# DC_DC_5V_1.net
KiCad netlist of a schematic drawn in Altium Designer
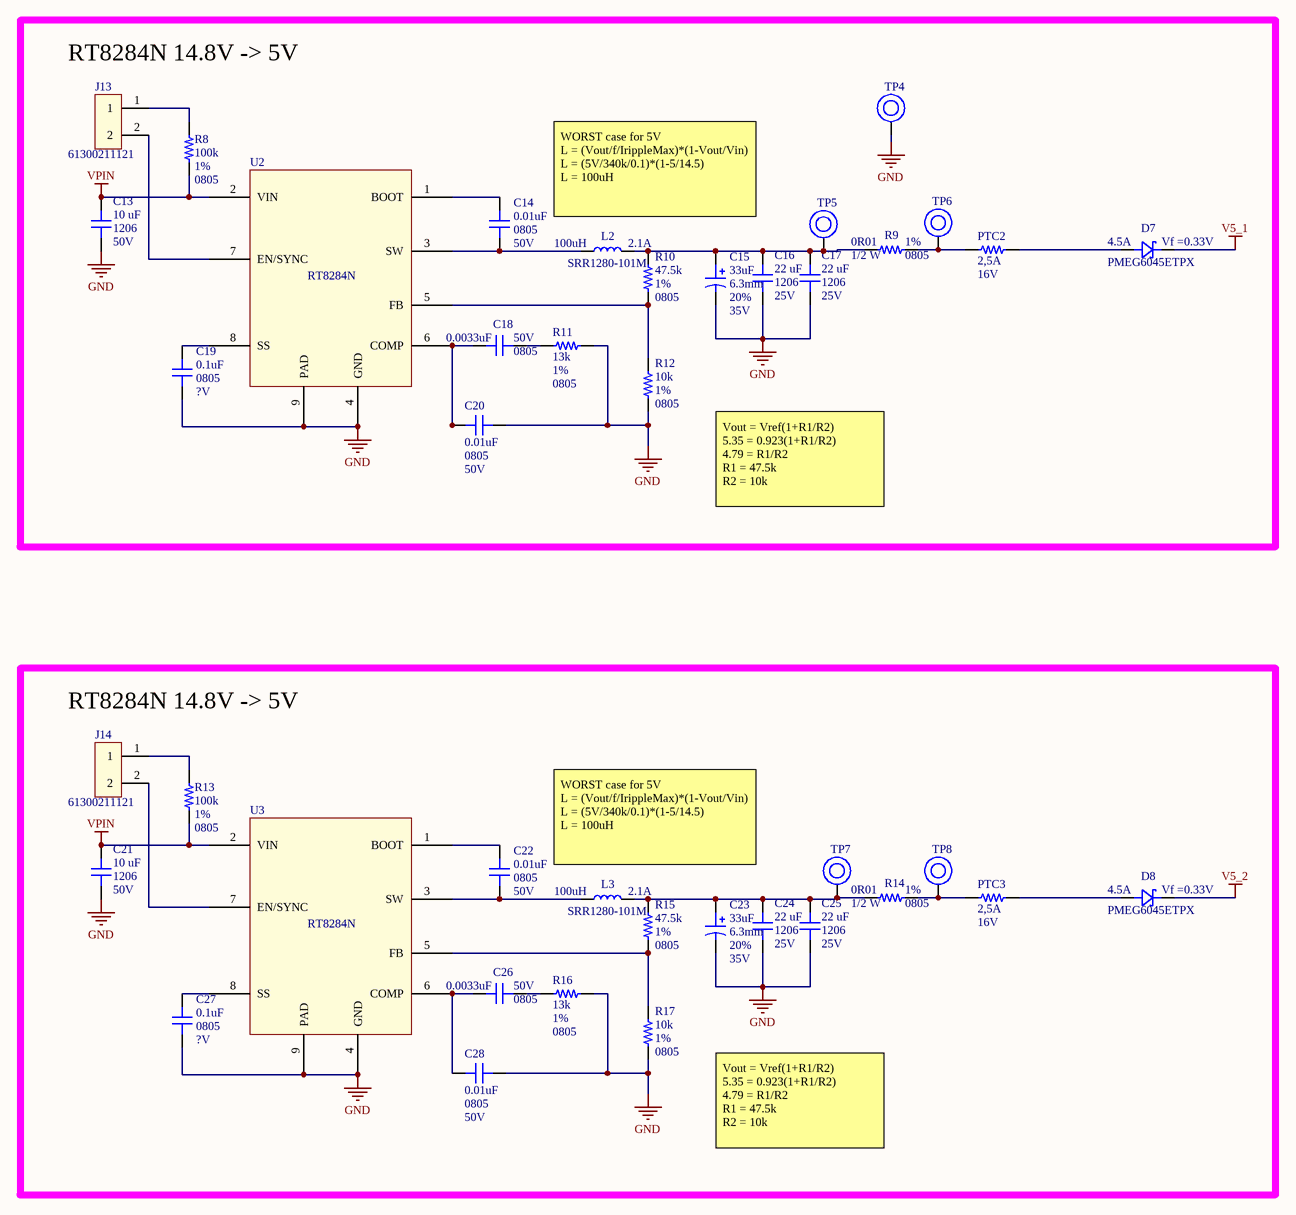
[diagram p0: DC_DC_5V_1.SchDoc]

(export (version "E")
  (design (tool "Eeschema 10.0.6"))
  (components
    (comp (ref "C13")
      (value "10 uF")
      (footprint "CAP_1206")
      (description "CAP - 1206")
      (fields
        (field (name "PACKAGE") "1206")
        (field (name "VOLTAGE") "50V")
        (field (name "PART NUMBER") "GRT31CR61H106ME01L")
      )
      (libsource (lib "SecureBot") (part "CAP - 1206"))
    )
    (comp (ref "C14")
      (value "0.01uF")
      (footprint "CAP_0805")
      (description "CAP - 0805")
      (fields
        (field (name "PART NUMBER") "CL21B103KBANNNC")
        (field (name "PACKAGE") "0805")
        (field (name "VOLTAGE") "50V")
      )
      (libsource (lib "SecureBot") (part "CAP - 0805"))
    )
    (comp (ref "C15")
      (value "33uF")
      (footprint "CAP ALU - 6.3mm DIA")
      (description "CAP ALU - 6.3mm")
      (fields
        (field (name "PACKAGE") "6.3mm")
        (field (name "TOLERANCE") "20%")
        (field (name "VOLTAGE") "35V")
        (field (name "PART NUMBER") "EEE-FK1V330P")
      )
      (libsource (lib "SecureBot") (part "CAP ALU - 6_3mm"))
    )
    (comp (ref "C16")
      (value "22 uF")
      (footprint "CAP_1206")
      (description "CAP - 1206")
      (fields
        (field (name "PACKAGE") "1206")
        (field (name "VOLTAGE") "25V")
        (field (name "PART NUMBER") "CL31A226KAHNNNE")
      )
      (libsource (lib "SecureBot") (part "CAP - 1206"))
    )
    (comp (ref "C17")
      (value "22 uF")
      (footprint "CAP_1206")
      (description "CAP - 1206")
      (fields
        (field (name "PACKAGE") "1206")
        (field (name "VOLTAGE") "25V")
        (field (name "PART NUMBER") "CL31A226KAHNNNE")
      )
      (libsource (lib "SecureBot") (part "CAP - 1206"))
    )
    (comp (ref "C18")
      (value "0.0033uF")
      (footprint "CAP_0805")
      (description "CAP - 0805")
      (fields
        (field (name "PART NUMBER") "CL21B332KBANNNC")
        (field (name "PACKAGE") "0805")
        (field (name "VOLTAGE") "50V")
      )
      (libsource (lib "SecureBot") (part "CAP - 0805"))
    )
    (comp (ref "C19")
      (value "0.1uF")
      (footprint "CAP_0805")
      (description "CAP - 0805")
      (fields
        (field (name "PART NUMBER") "CC0805KRX7R9BB104")
        (field (name "PACKAGE") "0805")
        (field (name "VOLTAGE") "?V")
      )
      (libsource (lib "SecureBot") (part "CAP - 0805"))
    )
    (comp (ref "C20")
      (value "0.01uF")
      (footprint "CAP_0805")
      (description "CAP - 0805")
      (fields
        (field (name "PART NUMBER") "CL21B103KBANNNC")
        (field (name "PACKAGE") "0805")
        (field (name "VOLTAGE") "50V")
      )
      (libsource (lib "SecureBot") (part "CAP - 0805"))
    )
    (comp (ref "C21")
      (value "10 uF")
      (footprint "CAP_1206")
      (description "CAP - 1206")
      (fields
        (field (name "PACKAGE") "1206")
        (field (name "VOLTAGE") "50V")
        (field (name "PART NUMBER") "GRT31CR61H106ME01L")
      )
      (libsource (lib "SecureBot") (part "CAP - 1206"))
    )
    (comp (ref "C22")
      (value "0.01uF")
      (footprint "CAP_0805")
      (description "CAP - 0805")
      (fields
        (field (name "PART NUMBER") "CL21B103KBANNNC")
        (field (name "PACKAGE") "0805")
        (field (name "VOLTAGE") "50V")
      )
      (libsource (lib "SecureBot") (part "CAP - 0805"))
    )
    (comp (ref "C23")
      (value "33uF")
      (footprint "CAP ALU - 6.3mm DIA")
      (description "CAP ALU - 6.3mm")
      (fields
        (field (name "PACKAGE") "6.3mm")
        (field (name "TOLERANCE") "20%")
        (field (name "VOLTAGE") "35V")
        (field (name "PART NUMBER") "EEE-FK1V330P")
      )
      (libsource (lib "SecureBot") (part "CAP ALU - 6_3mm"))
    )
    (comp (ref "C24")
      (value "22 uF")
      (footprint "CAP_1206")
      (description "CAP - 1206")
      (fields
        (field (name "PACKAGE") "1206")
        (field (name "VOLTAGE") "25V")
        (field (name "PART NUMBER") "CL31A226KAHNNNE")
      )
      (libsource (lib "SecureBot") (part "CAP - 1206"))
    )
    (comp (ref "C25")
      (value "22 uF")
      (footprint "CAP_1206")
      (description "CAP - 1206")
      (fields
        (field (name "PACKAGE") "1206")
        (field (name "VOLTAGE") "25V")
        (field (name "PART NUMBER") "CL31A226KAHNNNE")
      )
      (libsource (lib "SecureBot") (part "CAP - 1206"))
    )
    (comp (ref "C26")
      (value "0.0033uF")
      (footprint "CAP_0805")
      (description "CAP - 0805")
      (fields
        (field (name "PART NUMBER") "CL21B332KBANNNC")
        (field (name "PACKAGE") "0805")
        (field (name "VOLTAGE") "50V")
      )
      (libsource (lib "SecureBot") (part "CAP - 0805"))
    )
    (comp (ref "C27")
      (value "0.1uF")
      (footprint "CAP_0805")
      (description "CAP - 0805")
      (fields
        (field (name "PART NUMBER") "CC0805KRX7R9BB104")
        (field (name "PACKAGE") "0805")
        (field (name "VOLTAGE") "?V")
      )
      (libsource (lib "SecureBot") (part "CAP - 0805"))
    )
    (comp (ref "C28")
      (value "0.01uF")
      (footprint "CAP_0805")
      (description "CAP - 0805")
      (fields
        (field (name "PART NUMBER") "CL21B103KBANNNC")
        (field (name "PACKAGE") "0805")
        (field (name "VOLTAGE") "50V")
      )
      (libsource (lib "SecureBot") (part "CAP - 0805"))
    )
    (comp (ref "D7")
      (value "SCHOTTKEY")
      (footprint "DO-214AC_SOD128")
      (fields
        (field (name "CURRENT") "4.5A")
        (field (name "VF") "Vf =0.33V")
        (field (name "PART NUMBER") "PMEG6045ETPX")
      )
      (libsource (lib "SecureBot") (part "SCHOTTKEY"))
    )
    (comp (ref "D8")
      (value "SCHOTTKEY")
      (footprint "DO-214AC_SOD128")
      (fields
        (field (name "CURRENT") "4.5A")
        (field (name "VF") "Vf =0.33V")
        (field (name "PART NUMBER") "PMEG6045ETPX")
      )
      (libsource (lib "SecureBot") (part "SCHOTTKEY"))
    )
    (comp (ref "J13")
      (value "Header 2 pin SM")
      (footprint "HDR1X2")
      (fields (field (name "PART NUMBER") "61300211121"))
      (libsource (lib "SecureBot") (part "Header 2 pin SM"))
    )
    (comp (ref "J14")
      (value "Header 2 pin SM")
      (footprint "HDR1X2")
      (fields (field (name "PART NUMBER") "61300211121"))
      (libsource (lib "SecureBot") (part "Header 2 pin SM"))
    )
    (comp (ref "L2")
      (value "100uH")
      (footprint "BOURNS 12.5x12.5mm")
      (description "IND")
      (fields (field (name "CURRENT") "2.1A") (field (name "PART NUMBER") "SRR1280-101M"))
      (libsource (lib "SecureBot") (part "IND"))
    )
    (comp (ref "L3")
      (value "100uH")
      (footprint "BOURNS 12.5x12.5mm")
      (description "IND")
      (fields (field (name "CURRENT") "2.1A") (field (name "PART NUMBER") "SRR1280-101M"))
      (libsource (lib "SecureBot") (part "IND"))
    )
    (comp (ref "PTC2")
      (value "PTC - 1812")
      (footprint "PTC - 1812")
      (fields
        (field (name "PART NUMBER") "0ZCG0160BF2C")
        (field (name "TRIP VALUE") "2,5A")
        (field (name "VOLTAGE") "16V")
      )
      (libsource (lib "SecureBot") (part "PTC - 1812"))
    )
    (comp (ref "PTC3")
      (value "PTC - 1812")
      (footprint "PTC - 1812")
      (fields
        (field (name "PART NUMBER") "0ZCG0160BF2C")
        (field (name "TRIP VALUE") "2,5A")
        (field (name "VOLTAGE") "16V")
      )
      (libsource (lib "SecureBot") (part "PTC - 1812"))
    )
    (comp (ref "R8")
      (value "100k")
      (footprint "FER_0805")
      (description "RES - 0805")
      (fields
        (field (name "TOLERANCE") "1%")
        (field (name "PACKAGE") "0805")
        (field (name "PART NUMBER") "RMCF0805FT100K")
      )
      (libsource (lib "SecureBot") (part "RES - 0805"))
    )
    (comp (ref "R9")
      (value "0R01")
      (footprint "FER_0805")
      (description "RES - 0805")
      (fields
        (field (name "WATT") "1/2 W")
        (field (name "TOLERANCE") "1%")
        (field (name "PACKAGE") "0805")
        (field (name "PART NUMBER") "KRL1220E-M-R010-F-T5")
      )
      (libsource (lib "SecureBot") (part "RES - 0805"))
    )
    (comp (ref "R10")
      (value "47.5k")
      (footprint "FER_0805")
      (description "RES - 0805")
      (fields
        (field (name "TOLERANCE") "1%")
        (field (name "PACKAGE") "0805")
        (field (name "PART NUMBER") "RMCF0805FT47K5")
      )
      (libsource (lib "SecureBot") (part "RES - 0805"))
    )
    (comp (ref "R11")
      (value "13k")
      (footprint "FER_0805")
      (description "RES - 0805")
      (fields
        (field (name "TOLERANCE") "1%")
        (field (name "PACKAGE") "0805")
        (field (name "PART NUMBER") "RC0805FR-0713KL")
      )
      (libsource (lib "SecureBot") (part "RES - 0805"))
    )
    (comp (ref "R12")
      (value "10k")
      (footprint "FER_0805")
      (description "RES - 0805")
      (fields
        (field (name "TOLERANCE") "1%")
        (field (name "PACKAGE") "0805")
        (field (name "PART NUMBER") "RMCF0805FT10K0")
      )
      (libsource (lib "SecureBot") (part "RES - 0805"))
    )
    (comp (ref "R13")
      (value "100k")
      (footprint "FER_0805")
      (description "RES - 0805")
      (fields
        (field (name "TOLERANCE") "1%")
        (field (name "PACKAGE") "0805")
        (field (name "PART NUMBER") "RMCF0805FT100K")
      )
      (libsource (lib "SecureBot") (part "RES - 0805"))
    )
    (comp (ref "R14")
      (value "0R01")
      (footprint "FER_0805")
      (description "RES - 0805")
      (fields
        (field (name "WATT") "1/2 W")
        (field (name "TOLERANCE") "1%")
        (field (name "PACKAGE") "0805")
        (field (name "PART NUMBER") "KRL1220E-M-R010-F-T5")
      )
      (libsource (lib "SecureBot") (part "RES - 0805"))
    )
    (comp (ref "R15")
      (value "47.5k")
      (footprint "FER_0805")
      (description "RES - 0805")
      (fields
        (field (name "TOLERANCE") "1%")
        (field (name "PACKAGE") "0805")
        (field (name "PART NUMBER") "RMCF0805FT47K5")
      )
      (libsource (lib "SecureBot") (part "RES - 0805"))
    )
    (comp (ref "R16")
      (value "13k")
      (footprint "FER_0805")
      (description "RES - 0805")
      (fields
        (field (name "TOLERANCE") "1%")
        (field (name "PACKAGE") "0805")
        (field (name "PART NUMBER") "RC0805FR-0713KL")
      )
      (libsource (lib "SecureBot") (part "RES - 0805"))
    )
    (comp (ref "R17")
      (value "10k")
      (footprint "FER_0805")
      (description "RES - 0805")
      (fields
        (field (name "TOLERANCE") "1%")
        (field (name "PACKAGE") "0805")
        (field (name "PART NUMBER") "RMCF0805FT10K0")
      )
      (libsource (lib "SecureBot") (part "RES - 0805"))
    )
    (comp (ref "TP4")
      (value "TestPoint 3x3mm")
      (footprint "TestPoint 3X3mm")
      (libsource (lib "SecureBot") (part "TestPoint 3x3mm"))
    )
    (comp (ref "TP5")
      (value "TestPoint 3x3mm")
      (footprint "TestPoint 3X3mm")
      (libsource (lib "SecureBot") (part "TestPoint 3x3mm"))
    )
    (comp (ref "TP6")
      (value "TestPoint 3x3mm")
      (footprint "TestPoint 3X3mm")
      (libsource (lib "SecureBot") (part "TestPoint 3x3mm"))
    )
    (comp (ref "TP7")
      (value "TestPoint 3x3mm")
      (footprint "TestPoint 3X3mm")
      (libsource (lib "SecureBot") (part "TestPoint 3x3mm"))
    )
    (comp (ref "TP8")
      (value "TestPoint 3x3mm")
      (footprint "TestPoint 3X3mm")
      (libsource (lib "SecureBot") (part "TestPoint 3x3mm"))
    )
    (comp (ref "U2") (value "RT8284N") (footprint "SOP8") (libsource (lib "SecureBot") (part "RT8284N")))
    (comp (ref "U3") (value "RT8284N") (footprint "SOP8") (libsource (lib "SecureBot") (part "RT8284N")))
  )
  (nets
    (net (code "1") (name "GND") (class "Default")
      (node (ref "C13") (pin "2") (pinfunction "2_2") (pintype "passive"))
      (node (ref "C15") (pin "2") (pinfunction "2_2") (pintype "passive"))
      (node (ref "C16") (pin "2") (pinfunction "2_2") (pintype "passive"))
      (node (ref "C17") (pin "2") (pinfunction "2_2") (pintype "passive"))
      (node (ref "C19") (pin "2") (pinfunction "2_2") (pintype "passive"))
      (node (ref "C20") (pin "2") (pinfunction "2_2") (pintype "passive"))
      (node (ref "C21") (pin "2") (pinfunction "2_2") (pintype "passive"))
      (node (ref "C23") (pin "2") (pinfunction "2_2") (pintype "passive"))
      (node (ref "C24") (pin "2") (pinfunction "2_2") (pintype "passive"))
      (node (ref "C25") (pin "2") (pinfunction "2_2") (pintype "passive"))
      (node (ref "C27") (pin "2") (pinfunction "2_2") (pintype "passive"))
      (node (ref "C28") (pin "2") (pinfunction "2_2") (pintype "passive"))
      (node (ref "R11") (pin "2") (pinfunction "2_2") (pintype "passive"))
      (node (ref "R12") (pin "2") (pinfunction "2_2") (pintype "passive"))
      (node (ref "R16") (pin "2") (pinfunction "2_2") (pintype "passive"))
      (node (ref "R17") (pin "2") (pinfunction "2_2") (pintype "passive"))
      (node (ref "TP4") (pin "1") (pinfunction "1_1") (pintype "passive"))
      (node (ref "U2") (pin "4") (pinfunction "GND_4") (pintype "passive"))
      (node (ref "U2") (pin "9") (pinfunction "PAD_9") (pintype "passive"))
      (node (ref "U3") (pin "4") (pinfunction "GND_4") (pintype "passive"))
      (node (ref "U3") (pin "9") (pinfunction "PAD_9") (pintype "passive"))
    )
    (net (code "2") (name "Net-(C15-Pad1)") (class "Default")
      (node (ref "C15") (pin "1") (pinfunction "1_1") (pintype "passive"))
      (node (ref "C16") (pin "1") (pinfunction "1_1") (pintype "passive"))
      (node (ref "C17") (pin "1") (pinfunction "1_1") (pintype "passive"))
      (node (ref "L2") (pin "2") (pinfunction "2_2") (pintype "passive"))
      (node (ref "R10") (pin "1") (pinfunction "1_1") (pintype "passive"))
      (node (ref "R9") (pin "1") (pinfunction "1_1") (pintype "passive"))
      (node (ref "TP5") (pin "1") (pinfunction "1_1") (pintype "passive"))
    )
    (net (code "3") (name "Net-(C18-Pad2)") (class "Default")
      (node (ref "C18") (pin "2") (pinfunction "2_2") (pintype "passive"))
      (node (ref "R11") (pin "1") (pinfunction "1_1") (pintype "passive"))
    )
    (net (code "4") (name "Net-(C23-Pad1)") (class "Default")
      (node (ref "C23") (pin "1") (pinfunction "1_1") (pintype "passive"))
      (node (ref "C24") (pin "1") (pinfunction "1_1") (pintype "passive"))
      (node (ref "C25") (pin "1") (pinfunction "1_1") (pintype "passive"))
      (node (ref "L3") (pin "2") (pinfunction "2_2") (pintype "passive"))
      (node (ref "R14") (pin "1") (pinfunction "1_1") (pintype "passive"))
      (node (ref "R15") (pin "1") (pinfunction "1_1") (pintype "passive"))
      (node (ref "TP7") (pin "1") (pinfunction "1_1") (pintype "passive"))
    )
    (net (code "5") (name "Net-(C26-Pad2)") (class "Default")
      (node (ref "C26") (pin "2") (pinfunction "2_2") (pintype "passive"))
      (node (ref "R16") (pin "1") (pinfunction "1_1") (pintype "passive"))
    )
    (net (code "6") (name "Net-(D7-Pad1)") (class "Default")
      (node (ref "D7") (pin "1") (pinfunction "1_1") (pintype "passive"))
      (node (ref "PTC2") (pin "2") (pinfunction "2_2") (pintype "passive"))
    )
    (net (code "7") (name "Net-(D8-Pad1)") (class "Default")
      (node (ref "D8") (pin "1") (pinfunction "1_1") (pintype "passive"))
      (node (ref "PTC3") (pin "2") (pinfunction "2_2") (pintype "passive"))
    )
    (net (code "8") (name "Net-(J13-Pad1)") (class "Default")
      (node (ref "J13") (pin "1") (pinfunction "1_1") (pintype "passive"))
      (node (ref "R8") (pin "2") (pinfunction "2_2") (pintype "passive"))
    )
    (net (code "9") (name "Net-(J14-Pad1)") (class "Default")
      (node (ref "J14") (pin "1") (pinfunction "1_1") (pintype "passive"))
      (node (ref "R13") (pin "2") (pinfunction "2_2") (pintype "passive"))
    )
    (net (code "10") (name "Net-(PTC2-Pad1)") (class "Default")
      (node (ref "PTC2") (pin "1") (pinfunction "1_1") (pintype "passive"))
      (node (ref "R9") (pin "2") (pinfunction "2_2") (pintype "passive"))
      (node (ref "TP6") (pin "1") (pinfunction "1_1") (pintype "passive"))
    )
    (net (code "11") (name "Net-(PTC3-Pad1)") (class "Default")
      (node (ref "PTC3") (pin "1") (pinfunction "1_1") (pintype "passive"))
      (node (ref "R14") (pin "2") (pinfunction "2_2") (pintype "passive"))
      (node (ref "TP8") (pin "1") (pinfunction "1_1") (pintype "passive"))
    )
    (net (code "12") (name "Net-(U2-BOOT)") (class "Default")
      (node (ref "C14") (pin "1") (pinfunction "1_1") (pintype "passive"))
      (node (ref "U2") (pin "1") (pinfunction "BOOT_1") (pintype "passive"))
    )
    (net (code "13") (name "Net-(U2-COMP)") (class "Default")
      (node (ref "C18") (pin "1") (pinfunction "1_1") (pintype "passive"))
      (node (ref "C20") (pin "1") (pinfunction "1_1") (pintype "passive"))
      (node (ref "U2") (pin "6") (pinfunction "COMP_6") (pintype "passive"))
    )
    (net (code "14") (name "Net-(U2-EN{slash}SYNC)") (class "Default")
      (node (ref "J13") (pin "2") (pinfunction "2_2") (pintype "passive"))
      (node (ref "U2") (pin "7") (pinfunction "EN/SYNC_7") (pintype "passive"))
    )
    (net (code "15") (name "Net-(U2-FB)") (class "Default")
      (node (ref "R10") (pin "2") (pinfunction "2_2") (pintype "passive"))
      (node (ref "R12") (pin "1") (pinfunction "1_1") (pintype "passive"))
      (node (ref "U2") (pin "5") (pinfunction "FB_5") (pintype "passive"))
    )
    (net (code "16") (name "Net-(U2-SS)") (class "Default")
      (node (ref "C19") (pin "1") (pinfunction "1_1") (pintype "passive"))
      (node (ref "U2") (pin "8") (pinfunction "SS_8") (pintype "passive"))
    )
    (net (code "17") (name "Net-(U2-SW)") (class "Default")
      (node (ref "C14") (pin "2") (pinfunction "2_2") (pintype "passive"))
      (node (ref "L2") (pin "1") (pinfunction "1_1") (pintype "passive"))
      (node (ref "U2") (pin "3") (pinfunction "SW_3") (pintype "passive"))
    )
    (net (code "18") (name "Net-(U3-BOOT)") (class "Default")
      (node (ref "C22") (pin "1") (pinfunction "1_1") (pintype "passive"))
      (node (ref "U3") (pin "1") (pinfunction "BOOT_1") (pintype "passive"))
    )
    (net (code "19") (name "Net-(U3-COMP)") (class "Default")
      (node (ref "C26") (pin "1") (pinfunction "1_1") (pintype "passive"))
      (node (ref "C28") (pin "1") (pinfunction "1_1") (pintype "passive"))
      (node (ref "U3") (pin "6") (pinfunction "COMP_6") (pintype "passive"))
    )
    (net (code "20") (name "Net-(U3-EN{slash}SYNC)") (class "Default")
      (node (ref "J14") (pin "2") (pinfunction "2_2") (pintype "passive"))
      (node (ref "U3") (pin "7") (pinfunction "EN/SYNC_7") (pintype "passive"))
    )
    (net (code "21") (name "Net-(U3-FB)") (class "Default")
      (node (ref "R15") (pin "2") (pinfunction "2_2") (pintype "passive"))
      (node (ref "R17") (pin "1") (pinfunction "1_1") (pintype "passive"))
      (node (ref "U3") (pin "5") (pinfunction "FB_5") (pintype "passive"))
    )
    (net (code "22") (name "Net-(U3-SS)") (class "Default")
      (node (ref "C27") (pin "1") (pinfunction "1_1") (pintype "passive"))
      (node (ref "U3") (pin "8") (pinfunction "SS_8") (pintype "passive"))
    )
    (net (code "23") (name "Net-(U3-SW)") (class "Default")
      (node (ref "C22") (pin "2") (pinfunction "2_2") (pintype "passive"))
      (node (ref "L3") (pin "1") (pinfunction "1_1") (pintype "passive"))
      (node (ref "U3") (pin "3") (pinfunction "SW_3") (pintype "passive"))
    )
    (net (code "24") (name "V5_1") (class "Default")
      (node (ref "D7") (pin "2") (pinfunction "2_2") (pintype "passive"))
    )
    (net (code "25") (name "V5_2") (class "Default")
      (node (ref "D8") (pin "2") (pinfunction "2_2") (pintype "passive"))
    )
    (net (code "26") (name "VPIN") (class "Default")
      (node (ref "C13") (pin "1") (pinfunction "1_1") (pintype "passive"))
      (node (ref "C21") (pin "1") (pinfunction "1_1") (pintype "passive"))
      (node (ref "R13") (pin "1") (pinfunction "1_1") (pintype "passive"))
      (node (ref "R8") (pin "1") (pinfunction "1_1") (pintype "passive"))
      (node (ref "U2") (pin "2") (pinfunction "VIN_2") (pintype "passive"))
      (node (ref "U3") (pin "2") (pinfunction "VIN_2") (pintype "passive"))
    )
  )
)
